# neuron.net
KiCad netlist of a schematic drawn in EAGLE
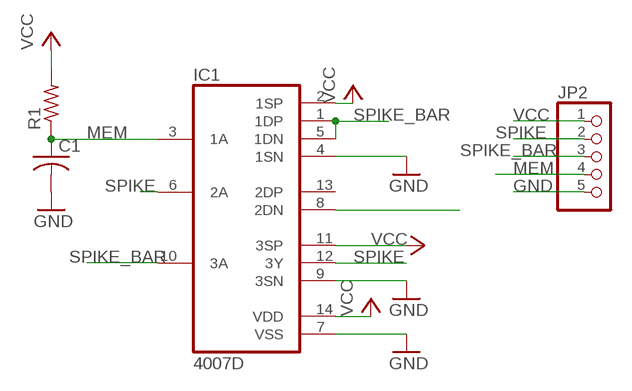
[diagram p0: schematic, sheet 1]

(export (version "E")
  (design (tool "Eeschema 10.0.6"))
  (components
    (comp (ref "C1")
      (value "C-USC0805")
      (footprint "eagle-import:C0805")
      (libsource (lib "eagle-import") (part "C-USC0805"))
    )
    (comp (ref "IC1")
      (value "4007D")
      (footprint "eagle-import:SO14")
      (libsource (lib "eagle-import") (part "4007D"))
    )
    (comp (ref "JP2")
      (value "PINHD-1X5")
      (footprint "eagle-import:1X05")
      (libsource (lib "eagle-import") (part "PINHD-1X5"))
    )
    (comp (ref "R1")
      (value "R-US_R0805")
      (footprint "eagle-import:R0805")
      (libsource (lib "eagle-import") (part "R-US_R0805"))
    )
  )
  (nets
    (net (code "1") (name "/MEM") (class "Default")
      (node (ref "C1") (pin "1") (pinfunction "1_1") (pintype "passive"))
      (node (ref "IC1") (pin "3") (pinfunction "1A_3") (pintype "input"))
      (node (ref "IC1") (pin "8") (pinfunction "2DN_8") (pintype "bidirectional"))
      (node (ref "JP2") (pin "4") (pinfunction "4_4") (pintype "passive"))
      (node (ref "R1") (pin "1") (pinfunction "1_1") (pintype "passive"))
    )
    (net (code "2") (name "/SPIKE") (class "Default")
      (node (ref "IC1") (pin "12") (pinfunction "3Y_12") (pintype "bidirectional"))
      (node (ref "IC1") (pin "6") (pinfunction "2A_6") (pintype "input"))
      (node (ref "JP2") (pin "2") (pinfunction "2_2") (pintype "passive"))
    )
    (net (code "3") (name "/SPIKE_BAR") (class "Default")
      (node (ref "IC1") (pin "1") (pinfunction "1DP_1") (pintype "open_collector"))
      (node (ref "IC1") (pin "10") (pinfunction "3A_10") (pintype "input"))
      (node (ref "IC1") (pin "5") (pinfunction "1DN_5") (pintype "open_collector"))
      (node (ref "JP2") (pin "3") (pinfunction "3_3") (pintype "passive"))
    )
    (net (code "4") (name "GND") (class "Default")
      (node (ref "C1") (pin "2") (pinfunction "2_2") (pintype "passive"))
      (node (ref "IC1") (pin "4") (pinfunction "1SN_4") (pintype "open_collector"))
      (node (ref "IC1") (pin "7") (pinfunction "VSS_7") (pintype "input"))
      (node (ref "IC1") (pin "9") (pinfunction "3SN_9") (pintype "bidirectional"))
      (node (ref "JP2") (pin "5") (pinfunction "5_5") (pintype "passive"))
    )
    (net (code "5") (name "VCC") (class "Default")
      (node (ref "IC1") (pin "11") (pinfunction "3SP_11") (pintype "bidirectional"))
      (node (ref "IC1") (pin "14") (pinfunction "VDD_14") (pintype "input"))
      (node (ref "IC1") (pin "2") (pinfunction "1SP_2") (pintype "open_collector"))
      (node (ref "JP2") (pin "1") (pinfunction "1_1") (pintype "passive"))
      (node (ref "R1") (pin "2") (pinfunction "2_2") (pintype "passive"))
    )
    (net (code "6") (name "unconnected-(IC1-2DP-Pad13)") (class "Default")
      (node (ref "IC1") (pin "13") (pinfunction "2DP_13") (pintype "bidirectional"))
    )
  )
)
